# Servo_and_Encoders.net
KiCad netlist of a schematic drawn in Altium Designer
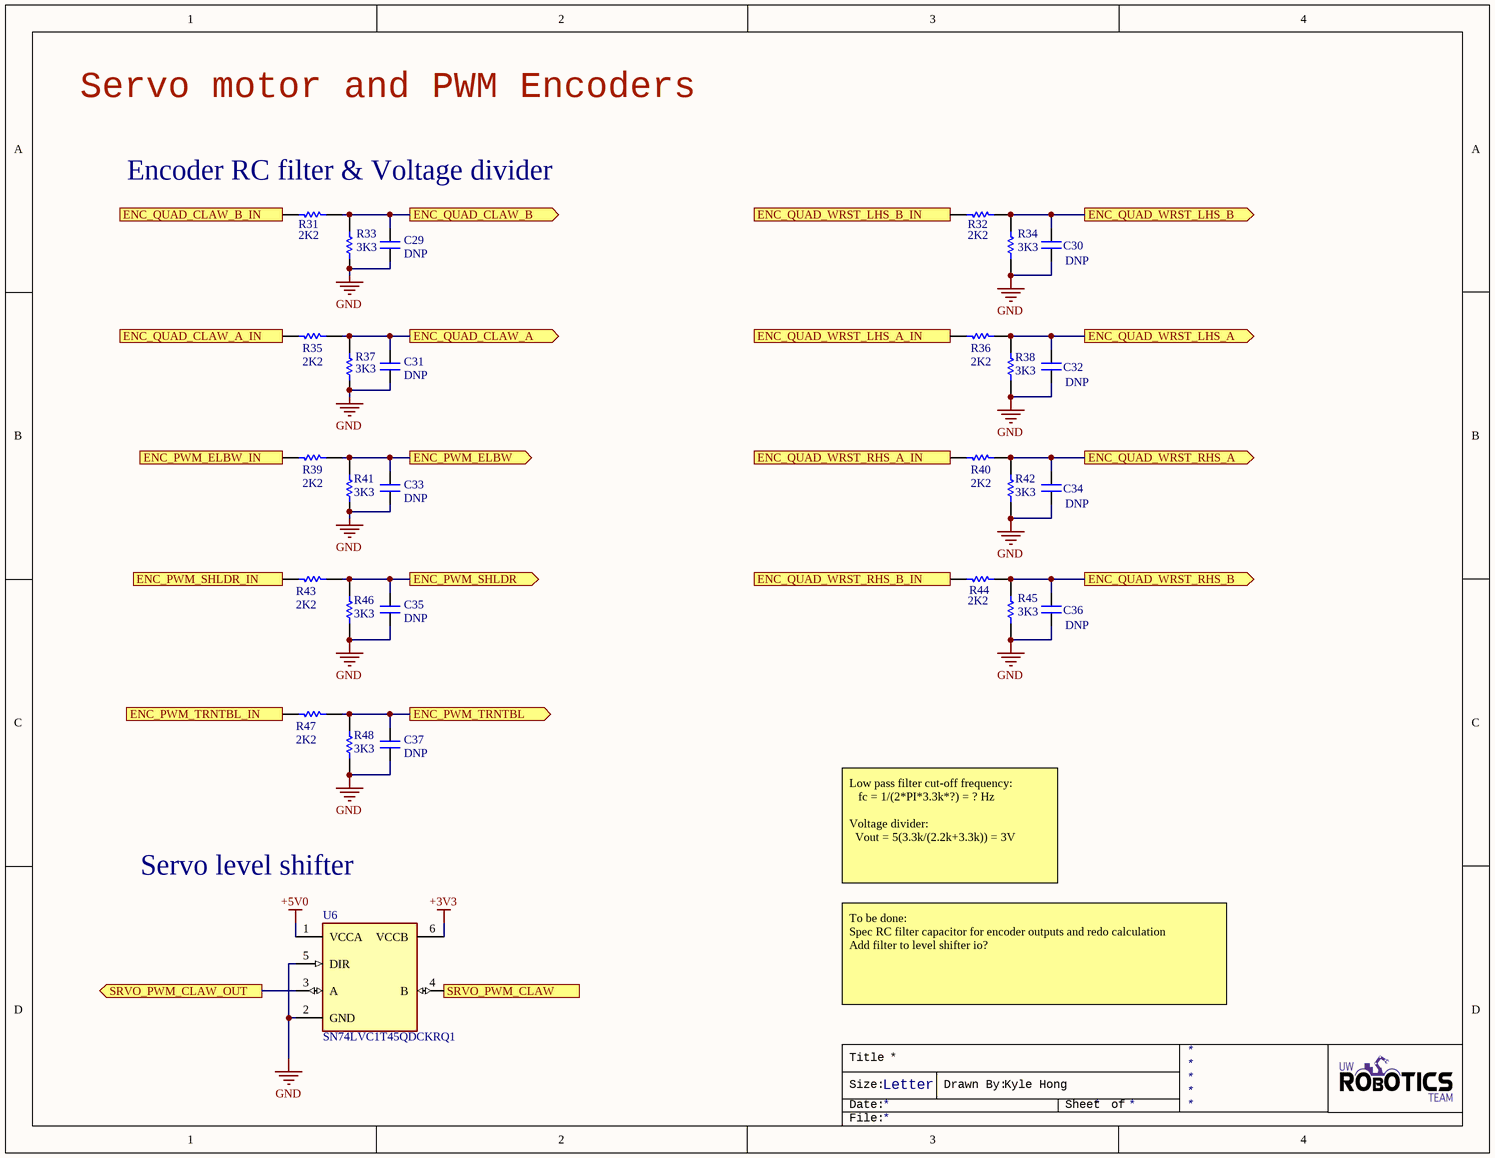
[diagram p0: Servo and Encoders.SchDoc]

(export (version "E")
  (design (tool "Eeschema 10.0.6"))
  (components
    (comp (ref "C29")
      (value "DNP")
      (footprint "CAPC0603(1608)55_N")
      (description "CAP DNP 0603")
      (fields (field (name "Comment") "CAP_DNP_0603_1_1"))
      (libsource (lib "UWRT_Schematic_Library_2020") (part "CAP_DNP_0603_1_1"))
    )
    (comp (ref "C30")
      (value "DNP")
      (footprint "CAPC0603(1608)55_N")
      (description "CAP DNP 0603")
      (fields (field (name "Comment") "CAP_DNP_0603_1_1"))
      (libsource (lib "UWRT_Schematic_Library_2020") (part "CAP_DNP_0603_1_1"))
    )
    (comp (ref "C31")
      (value "DNP")
      (footprint "CAPC0603(1608)55_N")
      (description "CAP DNP 0603")
      (fields (field (name "Comment") "CAP_DNP_0603_1_1"))
      (libsource (lib "UWRT_Schematic_Library_2020") (part "CAP_DNP_0603_1_1"))
    )
    (comp (ref "C32")
      (value "DNP")
      (footprint "CAPC0603(1608)55_N")
      (description "CAP DNP 0603")
      (fields (field (name "Comment") "CAP_DNP_0603_1_1"))
      (libsource (lib "UWRT_Schematic_Library_2020") (part "CAP_DNP_0603_1_1"))
    )
    (comp (ref "C33")
      (value "DNP")
      (footprint "CAPC0603(1608)55_N")
      (description "CAP DNP 0603")
      (fields (field (name "Comment") "CAP_DNP_0603_1_1"))
      (libsource (lib "UWRT_Schematic_Library_2020") (part "CAP_DNP_0603_1_1"))
    )
    (comp (ref "C34")
      (value "DNP")
      (footprint "CAPC0603(1608)55_N")
      (description "CAP DNP 0603")
      (fields (field (name "Comment") "CAP_DNP_0603_1_1"))
      (libsource (lib "UWRT_Schematic_Library_2020") (part "CAP_DNP_0603_1_1"))
    )
    (comp (ref "C35")
      (value "DNP")
      (footprint "CAPC0603(1608)55_N")
      (description "CAP DNP 0603")
      (fields (field (name "Comment") "CAP_DNP_0603_1_1"))
      (libsource (lib "UWRT_Schematic_Library_2020") (part "CAP_DNP_0603_1_1"))
    )
    (comp (ref "C36")
      (value "DNP")
      (footprint "CAPC0603(1608)55_N")
      (description "CAP DNP 0603")
      (fields (field (name "Comment") "CAP_DNP_0603_1_1"))
      (libsource (lib "UWRT_Schematic_Library_2020") (part "CAP_DNP_0603_1_1"))
    )
    (comp (ref "C37")
      (value "DNP")
      (footprint "CAPC0603(1608)55_N")
      (description "CAP DNP 0603")
      (fields (field (name "Comment") "CAP_DNP_0603_1_1"))
      (libsource (lib "UWRT_Schematic_Library_2020") (part "CAP_DNP_0603_1_1"))
    )
    (comp (ref "R31")
      (value "2K2")
      (footprint "RESC0603(1608)_N")
      (description "RES SMD 2.2K OHM 1% 1/10W 0603")
      (fields (field (name "MANUFACTURER") "Yageo") (field (name "TOLERANCE") "1%"))
      (libsource (lib "UWRT_Schematic_Library_2020") (part "RES_2K2_0603"))
    )
    (comp (ref "R32")
      (value "2K2")
      (footprint "RESC0603(1608)_N")
      (description "RES SMD 2.2K OHM 1% 1/10W 0603")
      (fields (field (name "MANUFACTURER") "Yageo") (field (name "TOLERANCE") "1%"))
      (libsource (lib "UWRT_Schematic_Library_2020") (part "RES_2K2_0603"))
    )
    (comp (ref "R33")
      (value "3K3")
      (footprint "RESC0603(1608)_N")
      (description "RES SMD 3.3K OHM 5% 1/10W 0603")
      (fields (field (name "MANUFACTURER") "Yageo") (field (name "TOLERANCE") "5%"))
      (libsource (lib "UWRT_Schematic_Library_2020") (part "RES_3K3_0603"))
    )
    (comp (ref "R34")
      (value "3K3")
      (footprint "RESC0603(1608)_N")
      (description "RES SMD 3.3K OHM 5% 1/10W 0603")
      (fields (field (name "MANUFACTURER") "Yageo") (field (name "TOLERANCE") "5%"))
      (libsource (lib "UWRT_Schematic_Library_2020") (part "RES_3K3_0603"))
    )
    (comp (ref "R35")
      (value "2K2")
      (footprint "RESC0603(1608)_N")
      (description "RES SMD 2.2K OHM 1% 1/10W 0603")
      (fields (field (name "MANUFACTURER") "Yageo") (field (name "TOLERANCE") "1%"))
      (libsource (lib "UWRT_Schematic_Library_2020") (part "RES_2K2_0603"))
    )
    (comp (ref "R36")
      (value "2K2")
      (footprint "RESC0603(1608)_N")
      (description "RES SMD 2.2K OHM 1% 1/10W 0603")
      (fields (field (name "MANUFACTURER") "Yageo") (field (name "TOLERANCE") "1%"))
      (libsource (lib "UWRT_Schematic_Library_2020") (part "RES_2K2_0603"))
    )
    (comp (ref "R37")
      (value "3K3")
      (footprint "RESC0603(1608)_N")
      (description "RES SMD 3.3K OHM 5% 1/10W 0603")
      (fields (field (name "MANUFACTURER") "Yageo") (field (name "TOLERANCE") "5%"))
      (libsource (lib "UWRT_Schematic_Library_2020") (part "RES_3K3_0603"))
    )
    (comp (ref "R38")
      (value "3K3")
      (footprint "RESC0603(1608)_N")
      (description "RES SMD 3.3K OHM 5% 1/10W 0603")
      (fields (field (name "MANUFACTURER") "Yageo") (field (name "TOLERANCE") "5%"))
      (libsource (lib "UWRT_Schematic_Library_2020") (part "RES_3K3_0603"))
    )
    (comp (ref "R39")
      (value "2K2")
      (footprint "RESC0603(1608)_N")
      (description "RES SMD 2.2K OHM 1% 1/10W 0603")
      (fields (field (name "MANUFACTURER") "Yageo") (field (name "TOLERANCE") "1%"))
      (libsource (lib "UWRT_Schematic_Library_2020") (part "RES_2K2_0603"))
    )
    (comp (ref "R40")
      (value "2K2")
      (footprint "RESC0603(1608)_N")
      (description "RES SMD 2.2K OHM 1% 1/10W 0603")
      (fields (field (name "MANUFACTURER") "Yageo") (field (name "TOLERANCE") "1%"))
      (libsource (lib "UWRT_Schematic_Library_2020") (part "RES_2K2_0603"))
    )
    (comp (ref "R41")
      (value "3K3")
      (footprint "RESC0603(1608)_N")
      (description "RES SMD 3.3K OHM 5% 1/10W 0603")
      (fields (field (name "MANUFACTURER") "Yageo") (field (name "TOLERANCE") "5%"))
      (libsource (lib "UWRT_Schematic_Library_2020") (part "RES_3K3_0603"))
    )
    (comp (ref "R42")
      (value "3K3")
      (footprint "RESC0603(1608)_N")
      (description "RES SMD 3.3K OHM 5% 1/10W 0603")
      (fields (field (name "MANUFACTURER") "Yageo") (field (name "TOLERANCE") "5%"))
      (libsource (lib "UWRT_Schematic_Library_2020") (part "RES_3K3_0603"))
    )
    (comp (ref "R43")
      (value "2K2")
      (footprint "RESC0603(1608)_N")
      (description "RES SMD 2.2K OHM 1% 1/10W 0603")
      (fields (field (name "MANUFACTURER") "Yageo") (field (name "TOLERANCE") "1%"))
      (libsource (lib "UWRT_Schematic_Library_2020") (part "RES_2K2_0603"))
    )
    (comp (ref "R44")
      (value "2K2")
      (footprint "RESC0603(1608)_N")
      (description "RES SMD 2.2K OHM 1% 1/10W 0603")
      (fields (field (name "MANUFACTURER") "Yageo") (field (name "TOLERANCE") "1%"))
      (libsource (lib "UWRT_Schematic_Library_2020") (part "RES_2K2_0603"))
    )
    (comp (ref "R45")
      (value "3K3")
      (footprint "RESC0603(1608)_N")
      (description "RES SMD 3.3K OHM 5% 1/10W 0603")
      (fields (field (name "MANUFACTURER") "Yageo") (field (name "TOLERANCE") "5%"))
      (libsource (lib "UWRT_Schematic_Library_2020") (part "RES_3K3_0603"))
    )
    (comp (ref "R46")
      (value "3K3")
      (footprint "RESC0603(1608)_N")
      (description "RES SMD 3.3K OHM 5% 1/10W 0603")
      (fields (field (name "MANUFACTURER") "Yageo") (field (name "TOLERANCE") "5%"))
      (libsource (lib "UWRT_Schematic_Library_2020") (part "RES_3K3_0603"))
    )
    (comp (ref "R47")
      (value "2K2")
      (footprint "RESC0603(1608)_N")
      (description "RES SMD 2.2K OHM 1% 1/10W 0603")
      (fields (field (name "MANUFACTURER") "Yageo") (field (name "TOLERANCE") "1%"))
      (libsource (lib "UWRT_Schematic_Library_2020") (part "RES_2K2_0603"))
    )
    (comp (ref "R48")
      (value "3K3")
      (footprint "RESC0603(1608)_N")
      (description "RES SMD 3.3K OHM 5% 1/10W 0603")
      (fields (field (name "MANUFACTURER") "Yageo") (field (name "TOLERANCE") "5%"))
      (libsource (lib "UWRT_Schematic_Library_2020") (part "RES_3K3_0603"))
    )
    (comp (ref "U6")
      (value "SN74LVC1T45QDCKRQ1")
      (footprint "SOT65P210X110-6N")
      (description "IC BIDIRECTIONAL LEVEL SHIFTER")
      (libsource (lib "UWRT_Schematic_Library_2020") (part "IC_LVL_SHIFTER_TI"))
    )
  )
  (nets
    (net (code "1") (name "+3V3") (class "Default")
      (node (ref "U6") (pin "6") (pinfunction "VCCB_6") (pintype "passive"))
    )
    (net (code "2") (name "+5V0") (class "Default")
      (node (ref "U6") (pin "1") (pinfunction "VCCA_1") (pintype "passive"))
    )
    (net (code "3") (name "/ENC_PWM_ELBW") (class "Default")
      (node (ref "C33") (pin "2") (pinfunction "2_2") (pintype "passive"))
      (node (ref "R39") (pin "1") (pinfunction "1_1") (pintype "passive"))
      (node (ref "R41") (pin "2") (pinfunction "2_2") (pintype "passive"))
    )
    (net (code "4") (name "/ENC_PWM_ELBW_IN") (class "Default")
      (node (ref "R39") (pin "2") (pinfunction "2_2") (pintype "passive"))
    )
    (net (code "5") (name "/ENC_PWM_SHLDR") (class "Default")
      (node (ref "C35") (pin "2") (pinfunction "2_2") (pintype "passive"))
      (node (ref "R43") (pin "1") (pinfunction "1_1") (pintype "passive"))
      (node (ref "R46") (pin "2") (pinfunction "2_2") (pintype "passive"))
    )
    (net (code "6") (name "/ENC_PWM_SHLDR_IN") (class "Default")
      (node (ref "R43") (pin "2") (pinfunction "2_2") (pintype "passive"))
    )
    (net (code "7") (name "/ENC_PWM_TRNTBL") (class "Default")
      (node (ref "C37") (pin "2") (pinfunction "2_2") (pintype "passive"))
      (node (ref "R47") (pin "1") (pinfunction "1_1") (pintype "passive"))
      (node (ref "R48") (pin "2") (pinfunction "2_2") (pintype "passive"))
    )
    (net (code "8") (name "/ENC_PWM_TRNTBL_IN") (class "Default")
      (node (ref "R47") (pin "2") (pinfunction "2_2") (pintype "passive"))
    )
    (net (code "9") (name "/ENC_QUAD_CLAW_A") (class "Default")
      (node (ref "C31") (pin "2") (pinfunction "2_2") (pintype "passive"))
      (node (ref "R35") (pin "1") (pinfunction "1_1") (pintype "passive"))
      (node (ref "R37") (pin "2") (pinfunction "2_2") (pintype "passive"))
    )
    (net (code "10") (name "/ENC_QUAD_CLAW_A_IN") (class "Default")
      (node (ref "R35") (pin "2") (pinfunction "2_2") (pintype "passive"))
    )
    (net (code "11") (name "/ENC_QUAD_CLAW_B") (class "Default")
      (node (ref "C29") (pin "2") (pinfunction "2_2") (pintype "passive"))
      (node (ref "R31") (pin "1") (pinfunction "1_1") (pintype "passive"))
      (node (ref "R33") (pin "2") (pinfunction "2_2") (pintype "passive"))
    )
    (net (code "12") (name "/ENC_QUAD_CLAW_B_IN") (class "Default")
      (node (ref "R31") (pin "2") (pinfunction "2_2") (pintype "passive"))
    )
    (net (code "13") (name "/ENC_QUAD_WRST_LHS_A") (class "Default")
      (node (ref "C32") (pin "2") (pinfunction "2_2") (pintype "passive"))
      (node (ref "R36") (pin "1") (pinfunction "1_1") (pintype "passive"))
      (node (ref "R38") (pin "2") (pinfunction "2_2") (pintype "passive"))
    )
    (net (code "14") (name "/ENC_QUAD_WRST_LHS_A_IN") (class "Default")
      (node (ref "R36") (pin "2") (pinfunction "2_2") (pintype "passive"))
    )
    (net (code "15") (name "/ENC_QUAD_WRST_LHS_B") (class "Default")
      (node (ref "C30") (pin "2") (pinfunction "2_2") (pintype "passive"))
      (node (ref "R32") (pin "1") (pinfunction "1_1") (pintype "passive"))
      (node (ref "R34") (pin "2") (pinfunction "2_2") (pintype "passive"))
    )
    (net (code "16") (name "/ENC_QUAD_WRST_LHS_B_IN") (class "Default")
      (node (ref "R32") (pin "2") (pinfunction "2_2") (pintype "passive"))
    )
    (net (code "17") (name "/ENC_QUAD_WRST_RHS_A") (class "Default")
      (node (ref "C34") (pin "2") (pinfunction "2_2") (pintype "passive"))
      (node (ref "R40") (pin "1") (pinfunction "1_1") (pintype "passive"))
      (node (ref "R42") (pin "2") (pinfunction "2_2") (pintype "passive"))
    )
    (net (code "18") (name "/ENC_QUAD_WRST_RHS_A_IN") (class "Default")
      (node (ref "R40") (pin "2") (pinfunction "2_2") (pintype "passive"))
    )
    (net (code "19") (name "/ENC_QUAD_WRST_RHS_B") (class "Default")
      (node (ref "C36") (pin "2") (pinfunction "2_2") (pintype "passive"))
      (node (ref "R44") (pin "1") (pinfunction "1_1") (pintype "passive"))
      (node (ref "R45") (pin "2") (pinfunction "2_2") (pintype "passive"))
    )
    (net (code "20") (name "/ENC_QUAD_WRST_RHS_B_IN") (class "Default")
      (node (ref "R44") (pin "2") (pinfunction "2_2") (pintype "passive"))
    )
    (net (code "21") (name "/SRVO_PWM_CLAW") (class "Default")
      (node (ref "U6") (pin "4") (pinfunction "B_4") (pintype "bidirectional"))
    )
    (net (code "22") (name "/SRVO_PWM_CLAW_OUT") (class "Default")
      (node (ref "U6") (pin "3") (pinfunction "A_3") (pintype "bidirectional"))
    )
    (net (code "23") (name "GND") (class "Default")
      (node (ref "C29") (pin "1") (pinfunction "1_1") (pintype "passive"))
      (node (ref "C30") (pin "1") (pinfunction "1_1") (pintype "passive"))
      (node (ref "C31") (pin "1") (pinfunction "1_1") (pintype "passive"))
      (node (ref "C32") (pin "1") (pinfunction "1_1") (pintype "passive"))
      (node (ref "C33") (pin "1") (pinfunction "1_1") (pintype "passive"))
      (node (ref "C34") (pin "1") (pinfunction "1_1") (pintype "passive"))
      (node (ref "C35") (pin "1") (pinfunction "1_1") (pintype "passive"))
      (node (ref "C36") (pin "1") (pinfunction "1_1") (pintype "passive"))
      (node (ref "C37") (pin "1") (pinfunction "1_1") (pintype "passive"))
      (node (ref "R33") (pin "1") (pinfunction "1_1") (pintype "passive"))
      (node (ref "R34") (pin "1") (pinfunction "1_1") (pintype "passive"))
      (node (ref "R37") (pin "1") (pinfunction "1_1") (pintype "passive"))
      (node (ref "R38") (pin "1") (pinfunction "1_1") (pintype "passive"))
      (node (ref "R41") (pin "1") (pinfunction "1_1") (pintype "passive"))
      (node (ref "R42") (pin "1") (pinfunction "1_1") (pintype "passive"))
      (node (ref "R45") (pin "1") (pinfunction "1_1") (pintype "passive"))
      (node (ref "R46") (pin "1") (pinfunction "1_1") (pintype "passive"))
      (node (ref "R48") (pin "1") (pinfunction "1_1") (pintype "passive"))
      (node (ref "U6") (pin "2") (pinfunction "GND_2") (pintype "passive"))
      (node (ref "U6") (pin "5") (pinfunction "DIR_5") (pintype "input"))
    )
  )
)
